# routev10_1.net
KiCad netlist of a schematic drawn in EAGLE
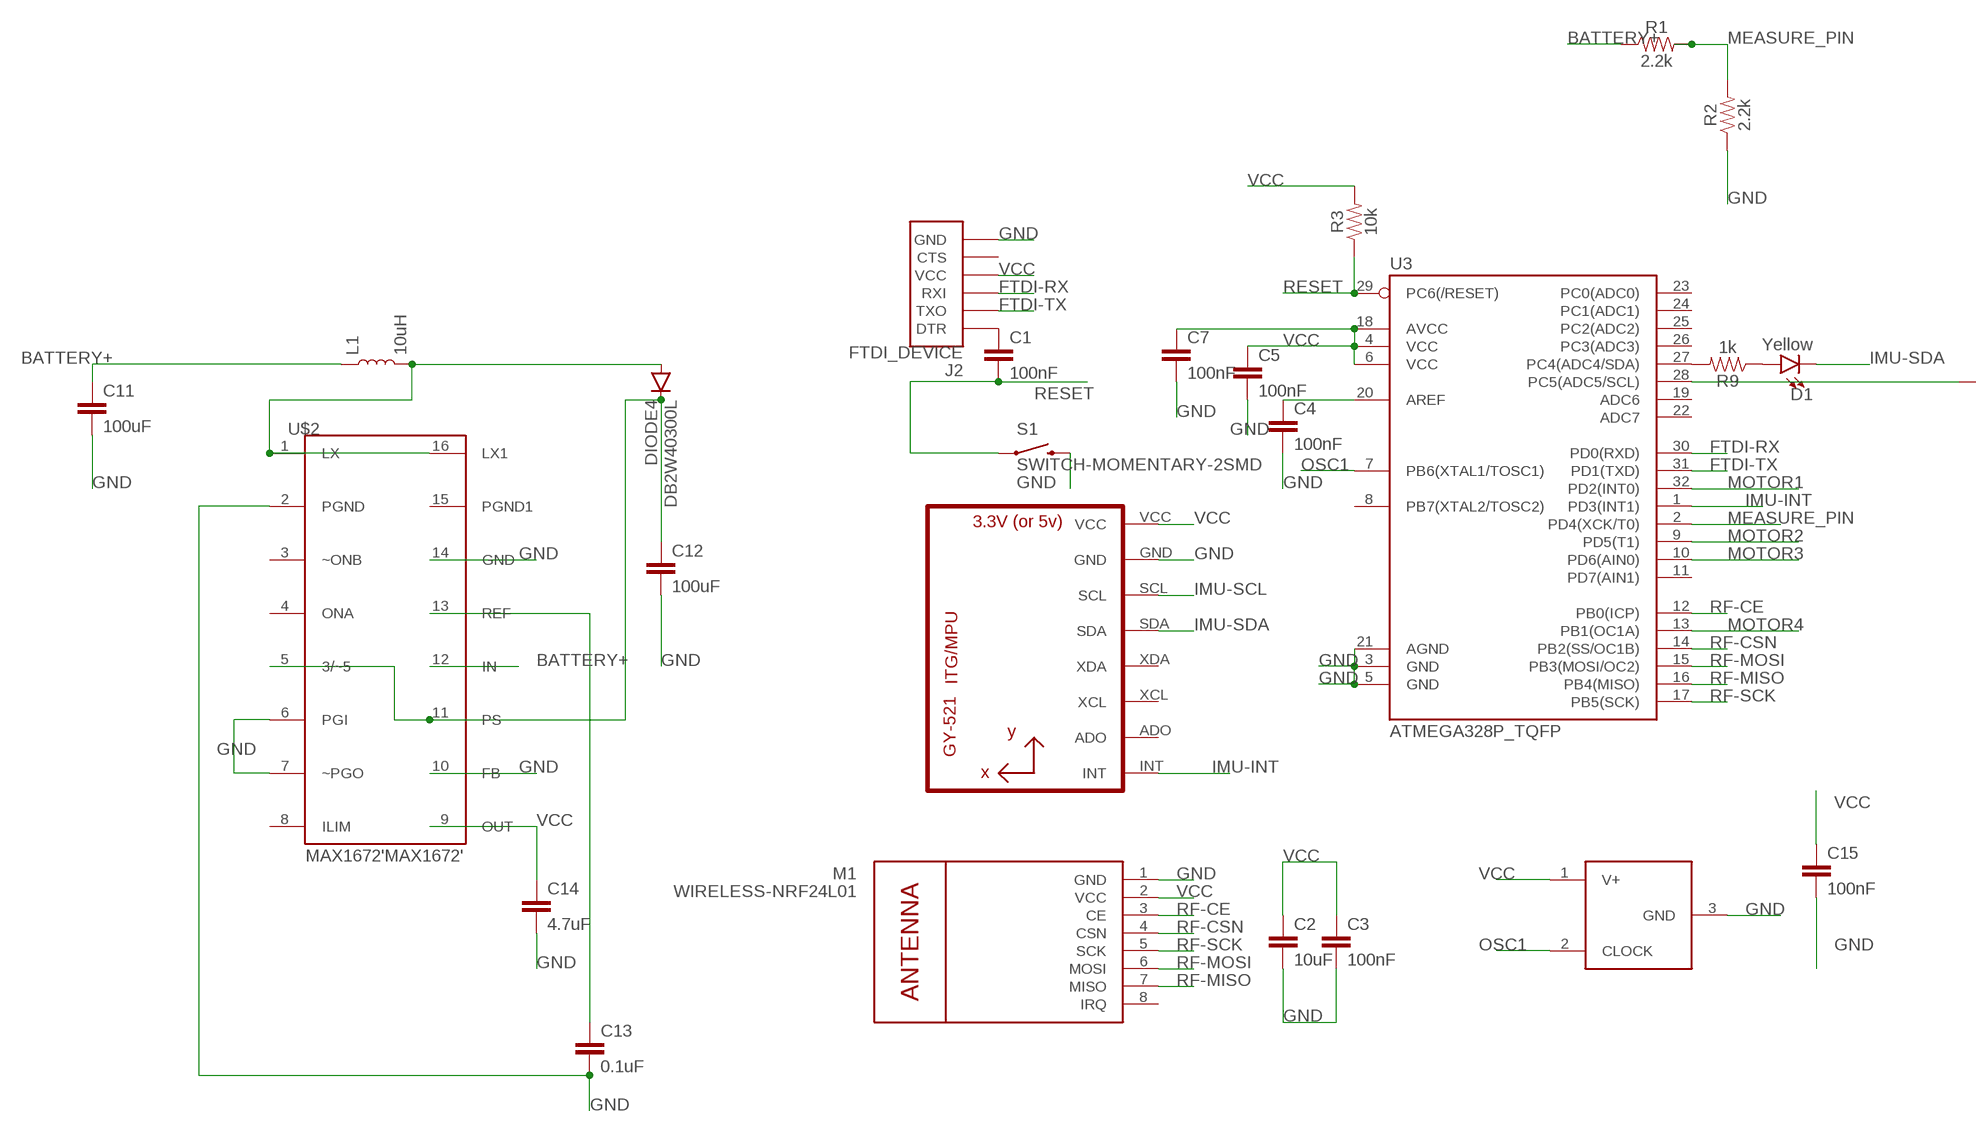
[diagram p0: schematic, sheet 1, part 1 of 2]
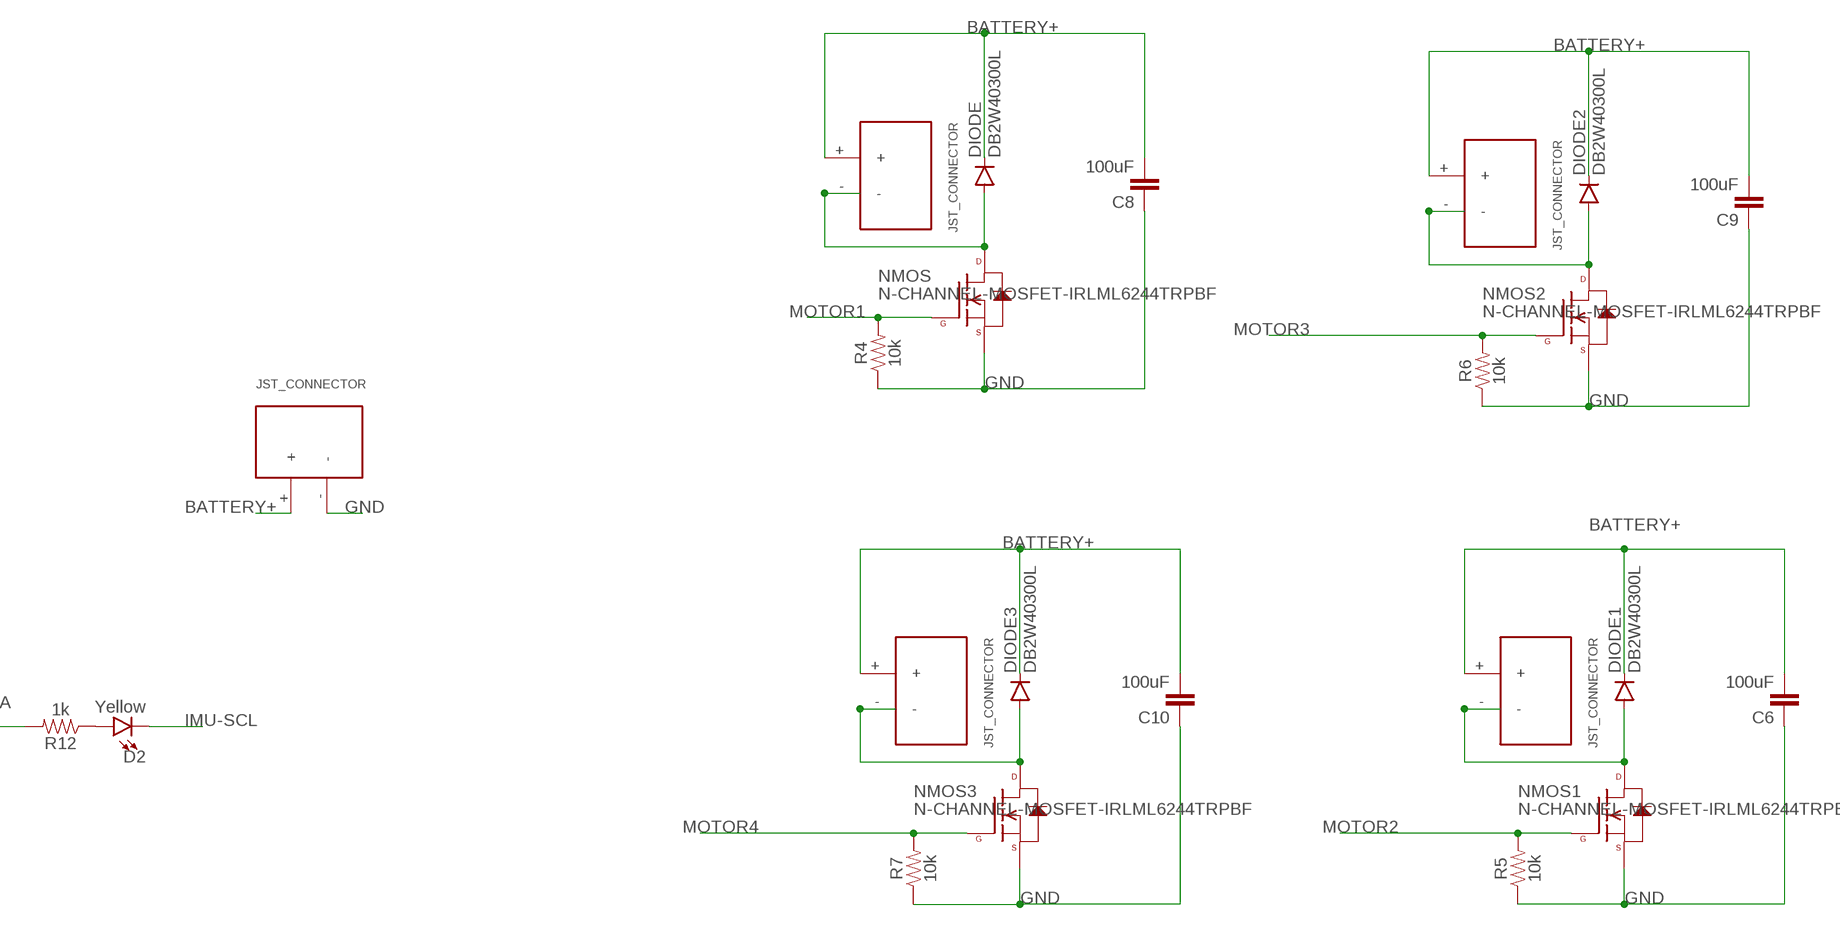
[diagram p1: schematic, sheet 1, part 2 of 2]

(export (version "E")
  (design (tool "Eeschema 10.0.6"))
  (components
    (comp (ref "AXR1")
      (value "MAX7375")
      (footprint "eagle-import:SC70-3L")
      (libsource (lib "eagle-import") (part "MAX7375"))
    )
    (comp (ref "C1")
      (value "100nF")
      (footprint "eagle-import:0603-CAP")
      (libsource (lib "eagle-import") (part "0.1UF-25V(+80/-20%)(0603)"))
    )
    (comp (ref "C2")
      (value "10uF")
      (footprint "eagle-import:0603-CAP")
      (libsource (lib "eagle-import") (part "CAP0603-CAP"))
    )
    (comp (ref "C3")
      (value "100nF")
      (footprint "eagle-import:0603-CAP")
      (libsource (lib "eagle-import") (part "CAP0603-CAP"))
    )
    (comp (ref "C4")
      (value "100nF")
      (footprint "eagle-import:0603-CAP")
      (libsource (lib "eagle-import") (part "CAP0603-CAP"))
    )
    (comp (ref "C5")
      (value "100nF")
      (footprint "eagle-import:0603-CAP")
      (libsource (lib "eagle-import") (part "CAP0603-CAP"))
    )
    (comp (ref "C6")
      (value "100uF")
      (footprint "eagle-import:0603-CAP")
      (libsource (lib "eagle-import") (part "CAP0603-CAP"))
    )
    (comp (ref "C7")
      (value "100nF")
      (footprint "eagle-import:0603-CAP")
      (libsource (lib "eagle-import") (part "CAP0603-CAP"))
    )
    (comp (ref "C8")
      (value "100uF")
      (footprint "eagle-import:0603-CAP")
      (libsource (lib "eagle-import") (part "CAP0603-CAP"))
    )
    (comp (ref "C9")
      (value "100uF")
      (footprint "eagle-import:0603-CAP")
      (libsource (lib "eagle-import") (part "CAP0603-CAP"))
    )
    (comp (ref "C10")
      (value "100uF")
      (footprint "eagle-import:0603-CAP")
      (libsource (lib "eagle-import") (part "CAP0603-CAP"))
    )
    (comp (ref "C11")
      (value "100uF")
      (footprint "eagle-import:0603-CAP")
      (libsource (lib "eagle-import") (part "CAP0603-CAP"))
    )
    (comp (ref "C12")
      (value "100uF")
      (footprint "eagle-import:0603-CAP")
      (libsource (lib "eagle-import") (part "CAP0603-CAP"))
    )
    (comp (ref "C13")
      (value "0.1uF")
      (footprint "eagle-import:0603-CAP")
      (libsource (lib "eagle-import") (part "CAP0603-CAP"))
    )
    (comp (ref "C14")
      (value "4.7uF")
      (footprint "eagle-import:0603-CAP")
      (libsource (lib "eagle-import") (part "CAP0603-CAP"))
    )
    (comp (ref "C15")
      (value "100nF")
      (footprint "eagle-import:0603-CAP")
      (libsource (lib "eagle-import") (part "0.1UF-25V(+80/-20%)(0603)"))
    )
    (comp (ref "D1")
      (value "Yellow")
      (footprint "eagle-import:LED-1206")
      (libsource (lib "eagle-import") (part "LED-YELLOWLILYPAD"))
    )
    (comp (ref "D2")
      (value "Yellow")
      (footprint "eagle-import:LED-1206")
      (libsource (lib "eagle-import") (part "LED-YELLOWLILYPAD"))
    )
    (comp (ref "DIODE")
      (value "DB2W40300L")
      (footprint "eagle-import:MINI2-F3-B")
      (libsource (lib "eagle-import") (part "DB2W40300L"))
    )
    (comp (ref "DIODE1")
      (value "DB2W40300L")
      (footprint "eagle-import:MINI2-F3-B")
      (libsource (lib "eagle-import") (part "DB2W40300L"))
    )
    (comp (ref "DIODE2")
      (value "DB2W40300L")
      (footprint "eagle-import:MINI2-F3-B")
      (libsource (lib "eagle-import") (part "DB2W40300L"))
    )
    (comp (ref "DIODE3")
      (value "DB2W40300L")
      (footprint "eagle-import:MINI2-F3-B")
      (libsource (lib "eagle-import") (part "DB2W40300L"))
    )
    (comp (ref "DIODE4")
      (value "DB2W40300L")
      (footprint "eagle-import:MINI2-F3-B")
      (libsource (lib "eagle-import") (part "DB2W40300L"))
    )
    (comp (ref "J2")
      (value "FTDI_DEVICE")
      (footprint "eagle-import:FTDI_DEVICE_SIDE")
      (libsource (lib "eagle-import") (part "FTDI_DEVICE"))
    )
    (comp (ref "L1")
      (value "10uH")
      (footprint "eagle-import:0603")
      (libsource (lib "eagle-import") (part "INDUCTOR-0603-33NH"))
    )
    (comp (ref "M1")
      (value "WIRELESS-NRF24L01")
      (footprint "eagle-import:WIRELESS-NRF24L01")
      (libsource (lib "eagle-import") (part "WIRELESS-NRF24L01"))
    )
    (comp (ref "MOTOR")
      (value "JST_CONNECTOR_FEMALE")
      (footprint "eagle-import:JST_CONNECTOR_FEMALE")
      (libsource (lib "eagle-import") (part "JST_CONNECTOR_FEMALE"))
    )
    (comp (ref "MOTOR2")
      (value "JST_CONNECTOR_FEMALE")
      (footprint "eagle-import:JST_CONNECTOR_FEMALE")
      (libsource (lib "eagle-import") (part "JST_CONNECTOR_FEMALE"))
    )
    (comp (ref "MOTOR3")
      (value "JST_CONNECTOR_FEMALE")
      (footprint "eagle-import:JST_CONNECTOR_FEMALE")
      (libsource (lib "eagle-import") (part "JST_CONNECTOR_FEMALE"))
    )
    (comp (ref "MOTOR4")
      (value "JST_CONNECTOR_FEMALE")
      (footprint "eagle-import:JST_CONNECTOR_FEMALE")
      (libsource (lib "eagle-import") (part "JST_CONNECTOR_FEMALE"))
    )
    (comp (ref "NMOS")
      (value "N-CHANNEL-MOSFET-IRLML6244TRPBF")
      (footprint "eagle-import:SOT23-3")
      (libsource (lib "eagle-import") (part "N-CHANNEL-MOSFET-IRLML6244TRPBF"))
    )
    (comp (ref "NMOS1")
      (value "N-CHANNEL-MOSFET-IRLML6244TRPBF")
      (footprint "eagle-import:SOT23-3")
      (libsource (lib "eagle-import") (part "N-CHANNEL-MOSFET-IRLML6244TRPBF"))
    )
    (comp (ref "NMOS2")
      (value "N-CHANNEL-MOSFET-IRLML6244TRPBF")
      (footprint "eagle-import:SOT23-3")
      (libsource (lib "eagle-import") (part "N-CHANNEL-MOSFET-IRLML6244TRPBF"))
    )
    (comp (ref "NMOS3")
      (value "N-CHANNEL-MOSFET-IRLML6244TRPBF")
      (footprint "eagle-import:SOT23-3")
      (libsource (lib "eagle-import") (part "N-CHANNEL-MOSFET-IRLML6244TRPBF"))
    )
    (comp (ref "R1")
      (value "2.2k")
      (footprint "eagle-import:0603")
      (libsource (lib "eagle-import") (part "2.2KOHM-0603-1/10W-1%"))
    )
    (comp (ref "R2")
      (value "2.2k")
      (footprint "eagle-import:0603")
      (libsource (lib "eagle-import") (part "2.2KOHM-0603-1/10W-1%"))
    )
    (comp (ref "R3")
      (value "10k")
      (footprint "eagle-import:0603")
      (libsource (lib "eagle-import") (part "2.2KOHM-0603-1/10W-1%"))
    )
    (comp (ref "R4")
      (value "10k")
      (footprint "eagle-import:0603")
      (libsource (lib "eagle-import") (part "2.2KOHM-0603-1/10W-1%"))
    )
    (comp (ref "R5")
      (value "10k")
      (footprint "eagle-import:0603")
      (libsource (lib "eagle-import") (part "2.2KOHM-0603-1/10W-1%"))
    )
    (comp (ref "R6")
      (value "10k")
      (footprint "eagle-import:0603")
      (libsource (lib "eagle-import") (part "2.2KOHM-0603-1/10W-1%"))
    )
    (comp (ref "R7")
      (value "10k")
      (footprint "eagle-import:0603")
      (libsource (lib "eagle-import") (part "2.2KOHM-0603-1/10W-1%"))
    )
    (comp (ref "R9")
      (value "1k")
      (footprint "eagle-import:0603")
      (libsource (lib "eagle-import") (part "2.2KOHM-0603-1/10W-1%"))
    )
    (comp (ref "R12")
      (value "1k")
      (footprint "eagle-import:0603")
      (libsource (lib "eagle-import") (part "2.2KOHM-0603-1/10W-1%"))
    )
    (comp (ref "S1")
      (value "SWITCH-MOMENTARY-2SMD")
      (footprint "eagle-import:TACTILE-SWITCH-SMD")
      (libsource (lib "eagle-import") (part "SWITCH-MOMENTARY-2SMD"))
    )
    (comp (ref "U$1")
      (value "JST_CONNECTOR_FEMALE")
      (footprint "eagle-import:JST_CONNECTOR_FEMALE")
      (libsource (lib "eagle-import") (part "JST_CONNECTOR_FEMALE"))
    )
    (comp (ref "U$2")
      (value "MAX1672'MAX1672'")
      (footprint "eagle-import:21-0055H_16")
      (libsource (lib "eagle-import") (part "MAX1672'MAX1672'"))
    )
    (comp (ref "U2")
      (value "GY-521MPU6050")
      (footprint "eagle-import:GY-521")
      (libsource (lib "eagle-import") (part "GY-521MPU6050"))
    )
    (comp (ref "U3")
      (value "ATMEGA328P_TQFP")
      (footprint "eagle-import:TQFP32-08")
      (libsource (lib "eagle-import") (part "ATMEGA328P_TQFP"))
    )
  )
  (nets
    (net (code "1") (name "BATTERY+") (class "Default")
      (node (ref "C10") (pin "2") (pinfunction "2_2") (pintype "passive"))
      (node (ref "C11") (pin "1") (pinfunction "1_1") (pintype "passive"))
      (node (ref "C6") (pin "2") (pinfunction "2_2") (pintype "passive"))
      (node (ref "C8") (pin "2") (pinfunction "2_2") (pintype "passive"))
      (node (ref "C9") (pin "2") (pinfunction "2_2") (pintype "passive"))
      (node (ref "DIODE") (pin "NEG") (pinfunction "GPIN_NEG") (pintype "passive"))
      (node (ref "DIODE1") (pin "NEG") (pinfunction "GPIN_NEG") (pintype "passive"))
      (node (ref "DIODE2") (pin "NEG") (pinfunction "GPIN_NEG") (pintype "passive"))
      (node (ref "DIODE3") (pin "NEG") (pinfunction "GPIN_NEG") (pintype "passive"))
      (node (ref "L1") (pin "1") (pinfunction "1_1") (pintype "passive"))
      (node (ref "MOTOR") (pin "+") (pinfunction "+_+") (pintype "bidirectional"))
      (node (ref "MOTOR2") (pin "+") (pinfunction "+_+") (pintype "bidirectional"))
      (node (ref "MOTOR3") (pin "+") (pinfunction "+_+") (pintype "bidirectional"))
      (node (ref "MOTOR4") (pin "+") (pinfunction "+_+") (pintype "bidirectional"))
      (node (ref "R1") (pin "1") (pinfunction "1_1") (pintype "passive"))
      (node (ref "U$1") (pin "+") (pinfunction "+_+") (pintype "bidirectional"))
      (node (ref "U$2") (pin "12") (pinfunction "IN_12") (pintype "bidirectional"))
    )
    (net (code "2") (name "FTDI-RX") (class "Default")
      (node (ref "J2") (pin "P$3") (pinfunction "RXI_P$3") (pintype "bidirectional"))
      (node (ref "U3") (pin "30") (pinfunction "PD0(RXD)_30") (pintype "bidirectional"))
    )
    (net (code "3") (name "FTDI-TX") (class "Default")
      (node (ref "J2") (pin "P$2") (pinfunction "TXO_P$2") (pintype "bidirectional"))
      (node (ref "U3") (pin "31") (pinfunction "PD1(TXD)_31") (pintype "bidirectional"))
    )
    (net (code "4") (name "GND") (class "Default")
      (node (ref "AXR1") (pin "3") (pinfunction "GND_3") (pintype "bidirectional"))
      (node (ref "C10") (pin "1") (pinfunction "1_1") (pintype "passive"))
      (node (ref "C11") (pin "2") (pinfunction "2_2") (pintype "passive"))
      (node (ref "C12") (pin "2") (pinfunction "2_2") (pintype "passive"))
      (node (ref "C13") (pin "2") (pinfunction "2_2") (pintype "passive"))
      (node (ref "C14") (pin "2") (pinfunction "2_2") (pintype "passive"))
      (node (ref "C15") (pin "2") (pinfunction "2_2") (pintype "passive"))
      (node (ref "C2") (pin "2") (pinfunction "2_2") (pintype "passive"))
      (node (ref "C3") (pin "2") (pinfunction "2_2") (pintype "passive"))
      (node (ref "C4") (pin "2") (pinfunction "2_2") (pintype "passive"))
      (node (ref "C5") (pin "2") (pinfunction "2_2") (pintype "passive"))
      (node (ref "C6") (pin "1") (pinfunction "1_1") (pintype "passive"))
      (node (ref "C7") (pin "2") (pinfunction "2_2") (pintype "passive"))
      (node (ref "C8") (pin "1") (pinfunction "1_1") (pintype "passive"))
      (node (ref "C9") (pin "1") (pinfunction "1_1") (pintype "passive"))
      (node (ref "J2") (pin "P$6") (pinfunction "GND_P$6") (pintype "bidirectional"))
      (node (ref "M1") (pin "1") (pinfunction "GND_1") (pintype "power_in"))
      (node (ref "NMOS") (pin "2") (pinfunction "S_2") (pintype "passive"))
      (node (ref "NMOS1") (pin "2") (pinfunction "S_2") (pintype "passive"))
      (node (ref "NMOS2") (pin "2") (pinfunction "S_2") (pintype "passive"))
      (node (ref "NMOS3") (pin "2") (pinfunction "S_2") (pintype "passive"))
      (node (ref "R2") (pin "1") (pinfunction "1_1") (pintype "passive"))
      (node (ref "R4") (pin "1") (pinfunction "1_1") (pintype "passive"))
      (node (ref "R5") (pin "1") (pinfunction "1_1") (pintype "passive"))
      (node (ref "R6") (pin "1") (pinfunction "1_1") (pintype "passive"))
      (node (ref "R7") (pin "1") (pinfunction "1_1") (pintype "passive"))
      (node (ref "S1") (pin "3") (pinfunction "2_3") (pintype "passive"))
      (node (ref "U$1") (pin "-") (pinfunction "-_-") (pintype "bidirectional"))
      (node (ref "U$2") (pin "10") (pinfunction "FB_10") (pintype "bidirectional"))
      (node (ref "U$2") (pin "14") (pinfunction "GND_14") (pintype "bidirectional"))
      (node (ref "U$2") (pin "2") (pinfunction "PGND_2") (pintype "bidirectional"))
      (node (ref "U$2") (pin "6") (pinfunction "PGI_6") (pintype "bidirectional"))
      (node (ref "U$2") (pin "7") (pinfunction "~{PGO}_7") (pintype "bidirectional"))
      (node (ref "U2") (pin "GND") (pinfunction "GND_GND") (pintype "bidirectional"))
      (node (ref "U3") (pin "21") (pinfunction "AGND_21") (pintype "bidirectional"))
      (node (ref "U3") (pin "3") (pinfunction "GND_3") (pintype "bidirectional"))
      (node (ref "U3") (pin "5") (pinfunction "GND_5") (pintype "bidirectional"))
    )
    (net (code "5") (name "IMU-INT") (class "Default")
      (node (ref "U2") (pin "INT") (pinfunction "INT_INT") (pintype "bidirectional"))
      (node (ref "U3") (pin "1") (pinfunction "PD3(INT1)_1") (pintype "bidirectional"))
    )
    (net (code "6") (name "IMU-SCL") (class "Default")
      (node (ref "D2") (pin "C") (pinfunction "C_C") (pintype "passive"))
      (node (ref "U2") (pin "SCL") (pinfunction "SCL_SCL") (pintype "bidirectional"))
    )
    (net (code "7") (name "IMU-SDA") (class "Default")
      (node (ref "D1") (pin "C") (pinfunction "C_C") (pintype "passive"))
      (node (ref "U2") (pin "SDA") (pinfunction "SDA_SDA") (pintype "bidirectional"))
    )
    (net (code "8") (name "MEASURE_PIN") (class "Default")
      (node (ref "R1") (pin "2") (pinfunction "2_2") (pintype "passive"))
      (node (ref "R2") (pin "2") (pinfunction "2_2") (pintype "passive"))
      (node (ref "U3") (pin "2") (pinfunction "PD4(XCK/T0)_2") (pintype "bidirectional"))
    )
    (net (code "9") (name "MOTOR1") (class "Default")
      (node (ref "NMOS") (pin "1") (pinfunction "G_1") (pintype "passive"))
      (node (ref "R4") (pin "2") (pinfunction "2_2") (pintype "passive"))
      (node (ref "U3") (pin "32") (pinfunction "PD2(INT0)_32") (pintype "bidirectional"))
    )
    (net (code "10") (name "MOTOR2") (class "Default")
      (node (ref "NMOS1") (pin "1") (pinfunction "G_1") (pintype "passive"))
      (node (ref "R5") (pin "2") (pinfunction "2_2") (pintype "passive"))
      (node (ref "U3") (pin "9") (pinfunction "PD5(T1)_9") (pintype "bidirectional"))
    )
    (net (code "11") (name "MOTOR3") (class "Default")
      (node (ref "NMOS2") (pin "1") (pinfunction "G_1") (pintype "passive"))
      (node (ref "R6") (pin "2") (pinfunction "2_2") (pintype "passive"))
      (node (ref "U3") (pin "10") (pinfunction "PD6(AIN0)_10") (pintype "bidirectional"))
    )
    (net (code "12") (name "MOTOR4") (class "Default")
      (node (ref "NMOS3") (pin "1") (pinfunction "G_1") (pintype "passive"))
      (node (ref "R7") (pin "2") (pinfunction "2_2") (pintype "passive"))
      (node (ref "U3") (pin "13") (pinfunction "PB1(OC1A)_13") (pintype "bidirectional"))
    )
    (net (code "13") (name "Net-(D1-PadA)") (class "Default")
      (node (ref "D1") (pin "A") (pinfunction "A_A") (pintype "passive"))
      (node (ref "R9") (pin "1") (pinfunction "1_1") (pintype "passive"))
    )
    (net (code "14") (name "Net-(D2-PadA)") (class "Default")
      (node (ref "D2") (pin "A") (pinfunction "A_A") (pintype "passive"))
      (node (ref "R12") (pin "1") (pinfunction "1_1") (pintype "passive"))
    )
    (net (code "15") (name "Net-(DIODE-PPIN)") (class "Default")
      (node (ref "DIODE") (pin "POS") (pinfunction "PPIN_POS") (pintype "passive"))
      (node (ref "MOTOR") (pin "-") (pinfunction "-_-") (pintype "bidirectional"))
      (node (ref "NMOS") (pin "3") (pinfunction "D_3") (pintype "passive"))
    )
    (net (code "16") (name "Net-(DIODE1-PPIN)") (class "Default")
      (node (ref "DIODE1") (pin "POS") (pinfunction "PPIN_POS") (pintype "passive"))
      (node (ref "MOTOR2") (pin "-") (pinfunction "-_-") (pintype "bidirectional"))
      (node (ref "NMOS1") (pin "3") (pinfunction "D_3") (pintype "passive"))
    )
    (net (code "17") (name "Net-(DIODE2-PPIN)") (class "Default")
      (node (ref "DIODE2") (pin "POS") (pinfunction "PPIN_POS") (pintype "passive"))
      (node (ref "MOTOR3") (pin "-") (pinfunction "-_-") (pintype "bidirectional"))
      (node (ref "NMOS2") (pin "3") (pinfunction "D_3") (pintype "passive"))
    )
    (net (code "18") (name "Net-(DIODE3-PPIN)") (class "Default")
      (node (ref "DIODE3") (pin "POS") (pinfunction "PPIN_POS") (pintype "passive"))
      (node (ref "MOTOR4") (pin "-") (pinfunction "-_-") (pintype "bidirectional"))
      (node (ref "NMOS3") (pin "3") (pinfunction "D_3") (pintype "passive"))
    )
    (net (code "19") (name "Net-(DIODE4-GPIN)") (class "Default")
      (node (ref "C12") (pin "1") (pinfunction "1_1") (pintype "passive"))
      (node (ref "DIODE4") (pin "NEG") (pinfunction "GPIN_NEG") (pintype "passive"))
      (node (ref "U$2") (pin "11") (pinfunction "PS_11") (pintype "bidirectional"))
      (node (ref "U$2") (pin "5") (pinfunction "3/~{5}_5") (pintype "bidirectional"))
    )
    (net (code "20") (name "Net-(DIODE4-PPIN)") (class "Default")
      (node (ref "DIODE4") (pin "POS") (pinfunction "PPIN_POS") (pintype "passive"))
      (node (ref "L1") (pin "2") (pinfunction "2_2") (pintype "passive"))
      (node (ref "U$2") (pin "1") (pinfunction "LX_1") (pintype "bidirectional"))
      (node (ref "U$2") (pin "16") (pinfunction "LX1_16") (pintype "bidirectional"))
    )
    (net (code "21") (name "Net-(J2-DTR)") (class "Default")
      (node (ref "C1") (pin "1") (pinfunction "1_1") (pintype "passive"))
      (node (ref "J2") (pin "P$1") (pinfunction "DTR_P$1") (pintype "bidirectional"))
    )
    (net (code "22") (name "Net-(U$2-REF)") (class "Default")
      (node (ref "C13") (pin "1") (pinfunction "1_1") (pintype "passive"))
      (node (ref "U$2") (pin "13") (pinfunction "REF_13") (pintype "bidirectional"))
    )
    (net (code "23") (name "Net-(U3-AREF)") (class "Default")
      (node (ref "C4") (pin "1") (pinfunction "1_1") (pintype "passive"))
      (node (ref "U3") (pin "20") (pinfunction "AREF_20") (pintype "bidirectional"))
    )
    (net (code "24") (name "Net-(U3-PC4(ADC4{slash}SDA))") (class "Default")
      (node (ref "R9") (pin "2") (pinfunction "2_2") (pintype "passive"))
      (node (ref "U3") (pin "27") (pinfunction "PC4(ADC4/SDA)_27") (pintype "bidirectional"))
    )
    (net (code "25") (name "Net-(U3-PC5(ADC5{slash}SCL))") (class "Default")
      (node (ref "R12") (pin "2") (pinfunction "2_2") (pintype "passive"))
      (node (ref "U3") (pin "28") (pinfunction "PC5(ADC5/SCL)_28") (pintype "bidirectional"))
    )
    (net (code "26") (name "OSC1") (class "Default")
      (node (ref "AXR1") (pin "2") (pinfunction "CLOCK_2") (pintype "bidirectional"))
      (node (ref "U3") (pin "7") (pinfunction "PB6(XTAL1/TOSC1)_7") (pintype "bidirectional"))
    )
    (net (code "27") (name "RESET") (class "Default")
      (node (ref "C1") (pin "2") (pinfunction "2_2") (pintype "passive"))
      (node (ref "R3") (pin "1") (pinfunction "1_1") (pintype "passive"))
      (node (ref "S1") (pin "1") (pinfunction "1_1") (pintype "passive"))
      (node (ref "U3") (pin "29") (pinfunction "PC6(/RESET)_29") (pintype "bidirectional"))
    )
    (net (code "28") (name "RF-CE") (class "Default")
      (node (ref "M1") (pin "3") (pinfunction "CE_3") (pintype "bidirectional"))
      (node (ref "U3") (pin "12") (pinfunction "PB0(ICP)_12") (pintype "bidirectional"))
    )
    (net (code "29") (name "RF-CSN") (class "Default")
      (node (ref "M1") (pin "4") (pinfunction "CSN_4") (pintype "bidirectional"))
      (node (ref "U3") (pin "14") (pinfunction "PB2(SS/OC1B)_14") (pintype "bidirectional"))
    )
    (net (code "30") (name "RF-MISO") (class "Default")
      (node (ref "M1") (pin "7") (pinfunction "MISO_7") (pintype "bidirectional"))
      (node (ref "U3") (pin "16") (pinfunction "PB4(MISO)_16") (pintype "bidirectional"))
    )
    (net (code "31") (name "RF-MOSI") (class "Default")
      (node (ref "M1") (pin "6") (pinfunction "MOSI_6") (pintype "bidirectional"))
      (node (ref "U3") (pin "15") (pinfunction "PB3(MOSI/OC2)_15") (pintype "bidirectional"))
    )
    (net (code "32") (name "RF-SCK") (class "Default")
      (node (ref "M1") (pin "5") (pinfunction "SCK_5") (pintype "bidirectional"))
      (node (ref "U3") (pin "17") (pinfunction "PB5(SCK)_17") (pintype "bidirectional"))
    )
    (net (code "33") (name "VCC") (class "Default")
      (node (ref "AXR1") (pin "1") (pinfunction "V+_1") (pintype "bidirectional"))
      (node (ref "C14") (pin "1") (pinfunction "1_1") (pintype "passive"))
      (node (ref "C15") (pin "1") (pinfunction "1_1") (pintype "passive"))
      (node (ref "C2") (pin "1") (pinfunction "1_1") (pintype "passive"))
      (node (ref "C3") (pin "1") (pinfunction "1_1") (pintype "passive"))
      (node (ref "C5") (pin "1") (pinfunction "1_1") (pintype "passive"))
      (node (ref "C7") (pin "1") (pinfunction "1_1") (pintype "passive"))
      (node (ref "J2") (pin "P$4") (pinfunction "VCC_P$4") (pintype "bidirectional"))
      (node (ref "M1") (pin "2") (pinfunction "VCC_2") (pintype "power_in"))
      (node (ref "R3") (pin "2") (pinfunction "2_2") (pintype "passive"))
      (node (ref "U$2") (pin "9") (pinfunction "OUT_9") (pintype "bidirectional"))
      (node (ref "U2") (pin "VCC") (pinfunction "VCC_VCC") (pintype "bidirectional"))
      (node (ref "U3") (pin "18") (pinfunction "AVCC_18") (pintype "bidirectional"))
      (node (ref "U3") (pin "4") (pinfunction "VCC_4") (pintype "bidirectional"))
      (node (ref "U3") (pin "6") (pinfunction "VCC_6") (pintype "bidirectional"))
    )
    (net (code "34") (name "unconnected-(J2-CTS-PadP$5)") (class "Default")
      (node (ref "J2") (pin "P$5") (pinfunction "CTS_P$5") (pintype "bidirectional"))
    )
    (net (code "35") (name "unconnected-(M1-IRQ-Pad8)") (class "Default")
      (node (ref "M1") (pin "8") (pinfunction "IRQ_8") (pintype "bidirectional"))
    )
    (net (code "36") (name "unconnected-(U$2-ILIM-Pad8)") (class "Default")
      (node (ref "U$2") (pin "8") (pinfunction "ILIM_8") (pintype "bidirectional"))
    )
    (net (code "37") (name "unconnected-(U$2-ONA-Pad4)") (class "Default")
      (node (ref "U$2") (pin "4") (pinfunction "ONA_4") (pintype "bidirectional"))
    )
    (net (code "38") (name "unconnected-(U$2-PGND1-Pad15)") (class "Default")
      (node (ref "U$2") (pin "15") (pinfunction "PGND1_15") (pintype "bidirectional"))
    )
    (net (code "39") (name "unconnected-(U$2-~{ONB}-Pad3)") (class "Default")
      (node (ref "U$2") (pin "3") (pinfunction "~{ONB}_3") (pintype "bidirectional"))
    )
    (net (code "40") (name "unconnected-(U2-PadADO)") (class "Default")
      (node (ref "U2") (pin "ADO") (pinfunction "ADO_ADO") (pintype "bidirectional"))
    )
    (net (code "41") (name "unconnected-(U2-PadXCL)") (class "Default")
      (node (ref "U2") (pin "XCL") (pinfunction "XCL_XCL") (pintype "bidirectional"))
    )
    (net (code "42") (name "unconnected-(U2-PadXDA)") (class "Default")
      (node (ref "U2") (pin "XDA") (pinfunction "XDA_XDA") (pintype "bidirectional"))
    )
    (net (code "43") (name "unconnected-(U3-ADC6-Pad19)") (class "Default")
      (node (ref "U3") (pin "19") (pinfunction "ADC6_19") (pintype "bidirectional"))
    )
    (net (code "44") (name "unconnected-(U3-ADC7-Pad22)") (class "Default")
      (node (ref "U3") (pin "22") (pinfunction "ADC7_22") (pintype "bidirectional"))
    )
    (net (code "45") (name "unconnected-(U3-PB7(XTAL2{slash}TOSC2)-Pad8)") (class "Default")
      (node (ref "U3") (pin "8") (pinfunction "PB7(XTAL2/TOSC2)_8") (pintype "bidirectional"))
    )
    (net (code "46") (name "unconnected-(U3-PC0(ADC0)-Pad23)") (class "Default")
      (node (ref "U3") (pin "23") (pinfunction "PC0(ADC0)_23") (pintype "bidirectional"))
    )
    (net (code "47") (name "unconnected-(U3-PC1(ADC1)-Pad24)") (class "Default")
      (node (ref "U3") (pin "24") (pinfunction "PC1(ADC1)_24") (pintype "bidirectional"))
    )
    (net (code "48") (name "unconnected-(U3-PC2(ADC2)-Pad25)") (class "Default")
      (node (ref "U3") (pin "25") (pinfunction "PC2(ADC2)_25") (pintype "bidirectional"))
    )
    (net (code "49") (name "unconnected-(U3-PC3(ADC3)-Pad26)") (class "Default")
      (node (ref "U3") (pin "26") (pinfunction "PC3(ADC3)_26") (pintype "bidirectional"))
    )
    (net (code "50") (name "unconnected-(U3-PD7(AIN1)-Pad11)") (class "Default")
      (node (ref "U3") (pin "11") (pinfunction "PD7(AIN1)_11") (pintype "bidirectional"))
    )
  )
)
